# TSOC_GROVEY_UART.net
KiCad netlist of a schematic drawn in EAGLE
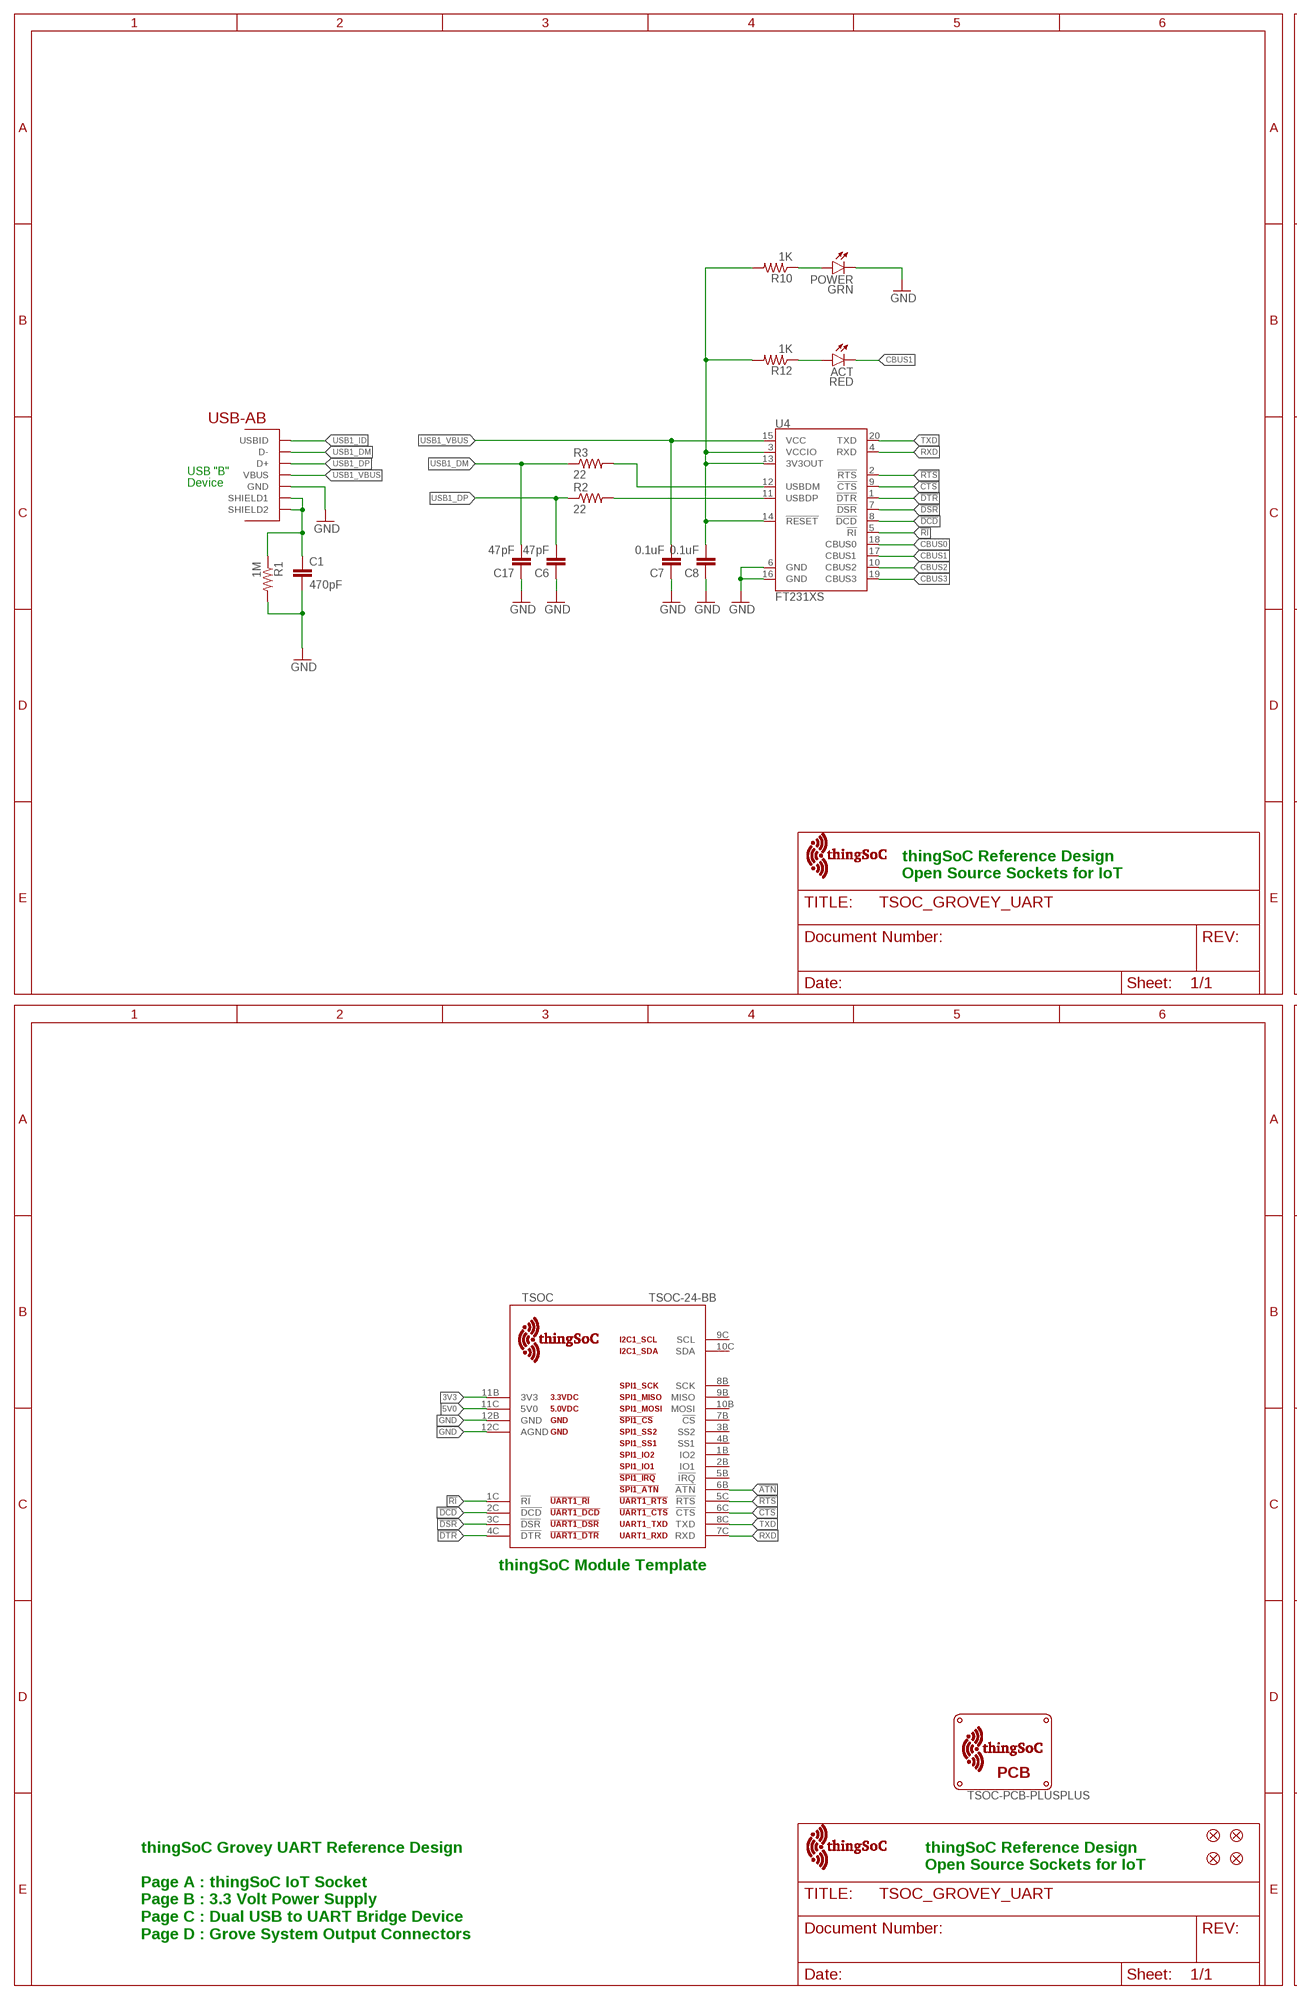
[diagram p0: schematic, sheet 1, part 1 of 2]
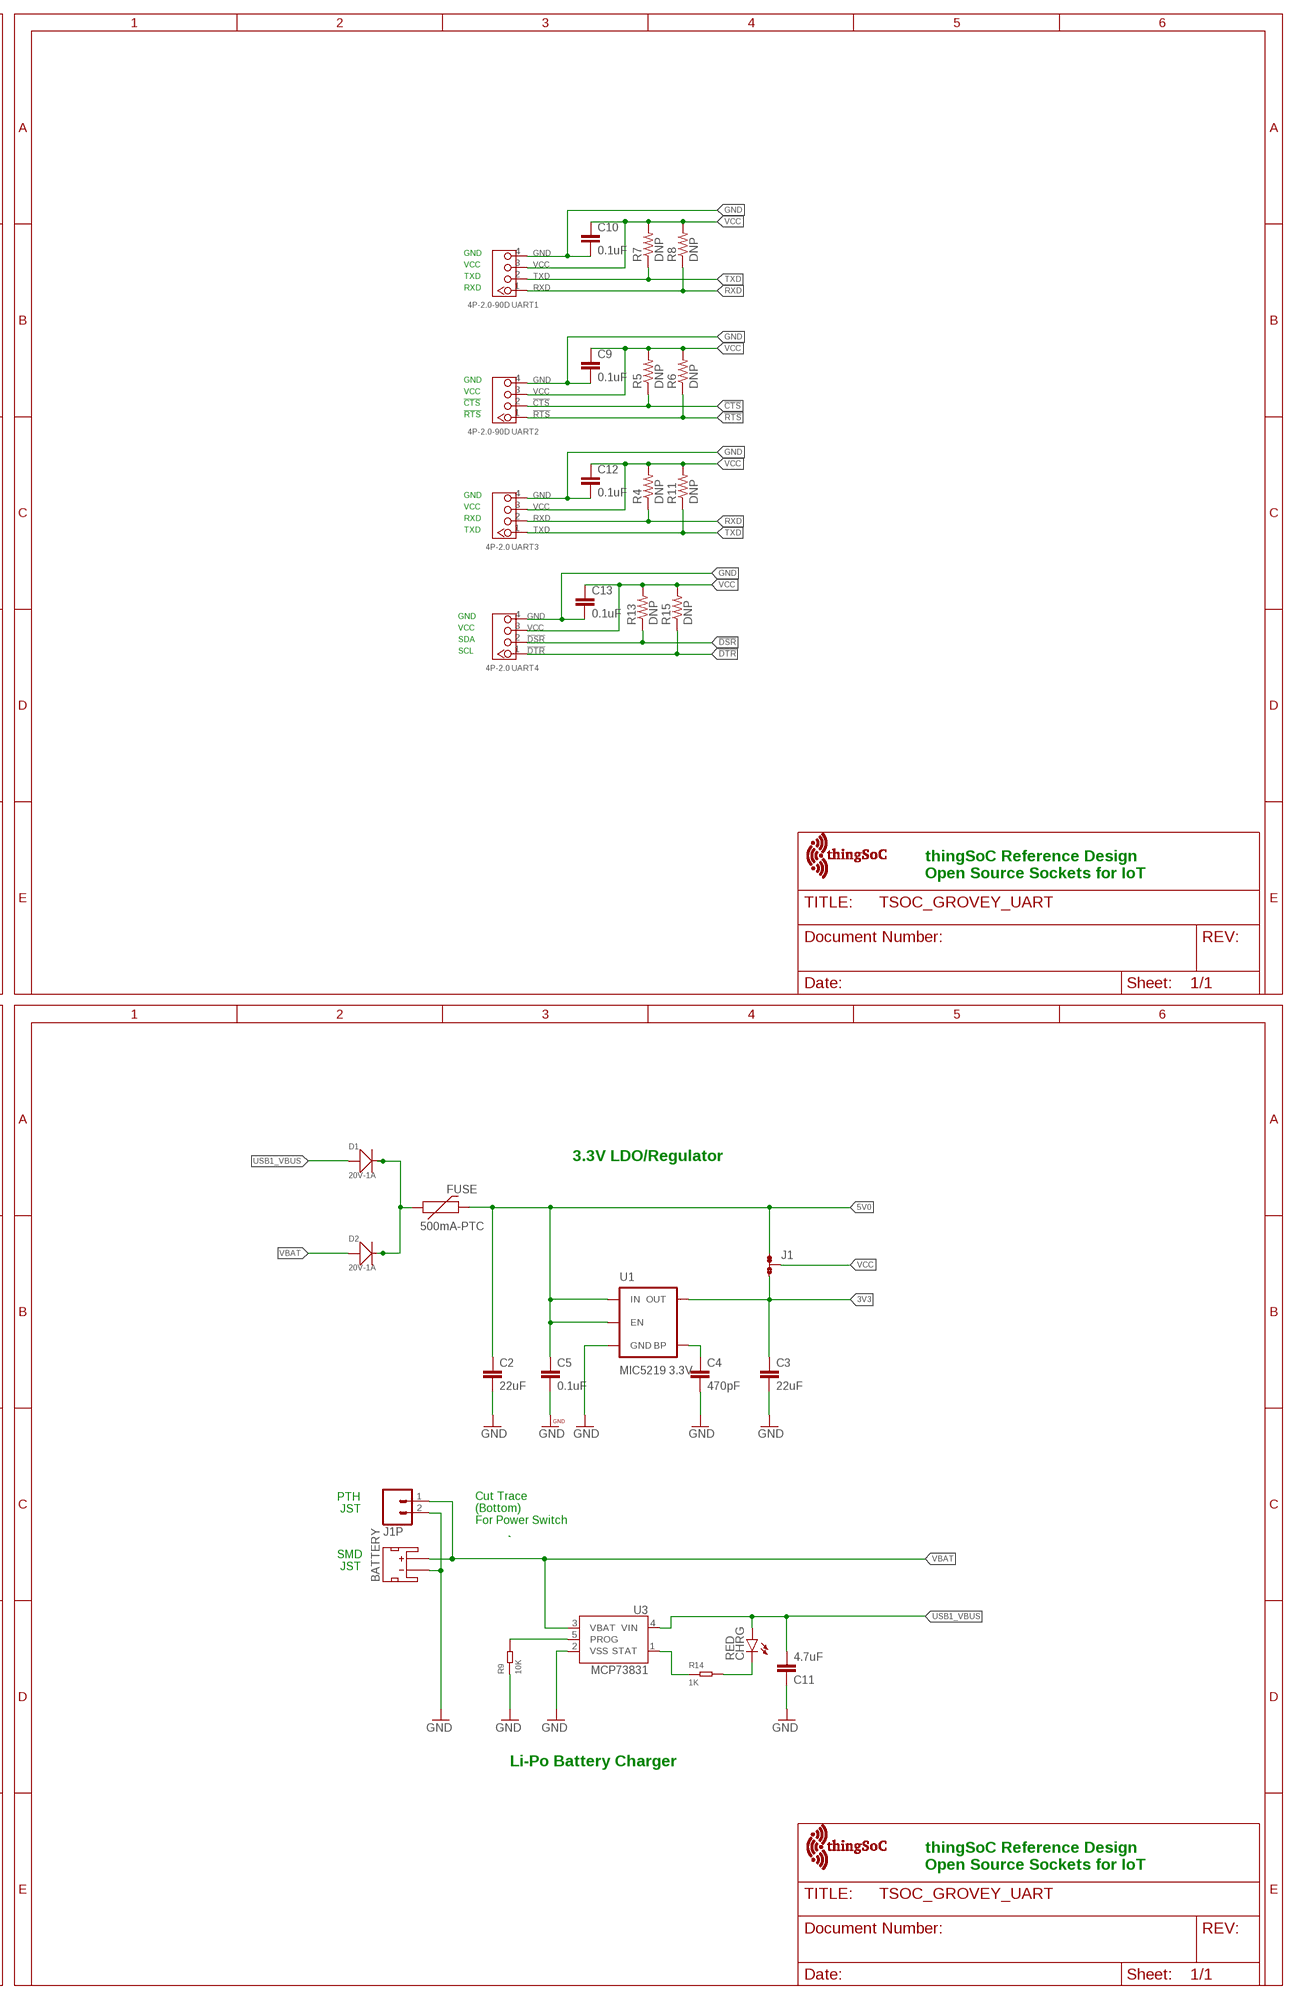
[diagram p1: schematic, sheet 1, part 2 of 2]

(export (version "E")
  (design (tool "Eeschema 10.0.6"))
  (components
    (comp (ref "ACT")
      (value "RED")
      (footprint "eagle-import:LED-0603")
      (libsource (lib "eagle-import") (part "LED0603"))
    )
    (comp (ref "BATTERY")
      (value "JST_2MM_MALE")
      (footprint "eagle-import:JST-2-SMD")
      (libsource (lib "eagle-import") (part "JST_2MM_MALE"))
    )
    (comp (ref "C1")
      (value "470pF")
      (footprint "eagle-import:EIA-0603")
      (libsource (lib "eagle-import") (part "CAP-0603"))
    )
    (comp (ref "C2")
      (value "22uF")
      (footprint "eagle-import:EIA-1206")
      (libsource (lib "eagle-import") (part "CAP-1206"))
    )
    (comp (ref "C3")
      (value "22uF")
      (footprint "eagle-import:EIA-1206")
      (libsource (lib "eagle-import") (part "CAP-1206"))
    )
    (comp (ref "C4")
      (value "470pF")
      (footprint "eagle-import:EIA-0603")
      (libsource (lib "eagle-import") (part "CAP-0603"))
    )
    (comp (ref "C5")
      (value "0.1uF")
      (footprint "eagle-import:EIA-0603")
      (libsource (lib "eagle-import") (part "CAP-0603"))
    )
    (comp (ref "C6")
      (value "47pF")
      (footprint "eagle-import:EIA-0603")
      (libsource (lib "eagle-import") (part "CAP-0603"))
    )
    (comp (ref "C7")
      (value "0.1uF")
      (footprint "eagle-import:EIA-0603")
      (libsource (lib "eagle-import") (part "CAP-0603"))
    )
    (comp (ref "C8")
      (value "0.1uF")
      (footprint "eagle-import:EIA-0603")
      (libsource (lib "eagle-import") (part "CAP-0603"))
    )
    (comp (ref "C9")
      (value "0.1uF")
      (footprint "eagle-import:0603-CAP")
      (libsource (lib "eagle-import") (part "CAP0603-CAP"))
    )
    (comp (ref "C10")
      (value "0.1uF")
      (footprint "eagle-import:0603-CAP")
      (libsource (lib "eagle-import") (part "CAP0603-CAP"))
    )
    (comp (ref "C11")
      (value "4.7uF")
      (footprint "eagle-import:0402-CAP")
      (libsource (lib "eagle-import") (part "TSOC-ESP8266-BASE_CAP0402-CAP"))
    )
    (comp (ref "C12")
      (value "0.1uF")
      (footprint "eagle-import:0603-CAP")
      (libsource (lib "eagle-import") (part "CAP0603-CAP"))
    )
    (comp (ref "C13")
      (value "0.1uF")
      (footprint "eagle-import:0603-CAP")
      (libsource (lib "eagle-import") (part "CAP0603-CAP"))
    )
    (comp (ref "C17")
      (value "47pF")
      (footprint "eagle-import:EIA-0603")
      (libsource (lib "eagle-import") (part "CAP-0603"))
    )
    (comp (ref "CHRG")
      (value "RED")
      (footprint "eagle-import:LED-0603")
      (libsource (lib "eagle-import") (part "LED0603"))
    )
    (comp (ref "D1")
      (value "20V-1A")
      (footprint "eagle-import:SOD-123")
      (fields (field (name "MPN") "B5819W"))
      (libsource (lib "eagle-import") (part "SMD-DIODE-SCHOTTKY-20V-1A(SOD-123)"))
    )
    (comp (ref "D2")
      (value "20V-1A")
      (footprint "eagle-import:SOD-123")
      (fields (field (name "MPN") "B5819W"))
      (libsource (lib "eagle-import") (part "SMD-DIODE-SCHOTTKY-20V-1A(SOD-123)"))
    )
    (comp (ref "FID1")
      (value "FIDUCIALUFIDUCIAL")
      (footprint "eagle-import:MICRO-FIDUCIAL")
      (libsource (lib "eagle-import") (part "FIDUCIALUFIDUCIAL"))
    )
    (comp (ref "FID2")
      (value "FIDUCIALUFIDUCIAL")
      (footprint "eagle-import:MICRO-FIDUCIAL")
      (libsource (lib "eagle-import") (part "FIDUCIALUFIDUCIAL"))
    )
    (comp (ref "FID3")
      (value "FIDUCIALUFIDUCIAL")
      (footprint "eagle-import:MICRO-FIDUCIAL")
      (libsource (lib "eagle-import") (part "FIDUCIALUFIDUCIAL"))
    )
    (comp (ref "FID4")
      (value "FIDUCIALUFIDUCIAL")
      (footprint "eagle-import:MICRO-FIDUCIAL")
      (libsource (lib "eagle-import") (part "FIDUCIALUFIDUCIAL"))
    )
    (comp (ref "FUSE")
      (value "500mA-PTC")
      (footprint "eagle-import:PTC-1206")
      (libsource (lib "eagle-import") (part "PTCSMD"))
    )
    (comp (ref "J1")
      (value "JMP-3-1_2")
      (footprint "eagle-import:JMP-3-1_2")
      (libsource (lib "eagle-import") (part "JMP-3-1_2"))
    )
    (comp (ref "J1P")
      (value "M02-JST-2-PTH-NO_SILK")
      (footprint "eagle-import:JST-2-PTH-NS")
      (libsource (lib "eagle-import") (part "M02-JST-2-PTH-NO_SILK"))
    )
    (comp (ref "POWER")
      (value "GRN")
      (footprint "eagle-import:LED-0603")
      (libsource (lib "eagle-import") (part "LED0603"))
    )
    (comp (ref "R1")
      (value "1M")
      (footprint "eagle-import:EIA-0603")
      (libsource (lib "eagle-import") (part "RESISTOR-0603"))
    )
    (comp (ref "R2")
      (value "22")
      (footprint "eagle-import:EIA-0603")
      (libsource (lib "eagle-import") (part "RESISTOR-0603"))
    )
    (comp (ref "R3")
      (value "22")
      (footprint "eagle-import:EIA-0603")
      (libsource (lib "eagle-import") (part "RESISTOR-0603"))
    )
    (comp (ref "R4")
      (value "DNP")
      (footprint "eagle-import:0603-RES")
      (libsource (lib "eagle-import") (part "RESISTOR0603-RES"))
    )
    (comp (ref "R5")
      (value "DNP")
      (footprint "eagle-import:0603-RES")
      (libsource (lib "eagle-import") (part "RESISTOR0603-RES"))
    )
    (comp (ref "R6")
      (value "DNP")
      (footprint "eagle-import:0603-RES")
      (libsource (lib "eagle-import") (part "RESISTOR0603-RES"))
    )
    (comp (ref "R7")
      (value "DNP")
      (footprint "eagle-import:0603-RES")
      (libsource (lib "eagle-import") (part "RESISTOR0603-RES"))
    )
    (comp (ref "R8")
      (value "DNP")
      (footprint "eagle-import:0603-RES")
      (libsource (lib "eagle-import") (part "RESISTOR0603-RES"))
    )
    (comp (ref "R9")
      (value "10K")
      (footprint "eagle-import:R0603")
      (fields (field (name "MPN") "RC0603FR-0710KL"))
      (libsource (lib "eagle-import") (part "SMD-RES-10K-1%-1/10W(0603)"))
    )
    (comp (ref "R10")
      (value "1K")
      (footprint "eagle-import:EIA-0603")
      (libsource (lib "eagle-import") (part "RESISTOR-0603"))
    )
    (comp (ref "R11")
      (value "DNP")
      (footprint "eagle-import:0603-RES")
      (libsource (lib "eagle-import") (part "RESISTOR0603-RES"))
    )
    (comp (ref "R12")
      (value "1K")
      (footprint "eagle-import:EIA-0603")
      (libsource (lib "eagle-import") (part "RESISTOR-0603"))
    )
    (comp (ref "R13")
      (value "DNP")
      (footprint "eagle-import:0603-RES")
      (libsource (lib "eagle-import") (part "RESISTOR0603-RES"))
    )
    (comp (ref "R14")
      (value "1K")
      (footprint "eagle-import:R0603")
      (fields (field (name "MPN") "RC0603FR-071KL"))
      (libsource (lib "eagle-import") (part "SMD-RES-1K-1%-1/10W(0603)"))
    )
    (comp (ref "R15")
      (value "DNP")
      (footprint "eagle-import:0603-RES")
      (libsource (lib "eagle-import") (part "RESISTOR0603-RES"))
    )
    (comp (ref "TSOC")
      (value "TSOC-24-BB")
      (footprint "eagle-import:TSOC-BB-S24")
      (libsource (lib "eagle-import") (part "TSOC-24-BB"))
    )
    (comp (ref "U$3")
      (value "TSOC-LOGO-LRG")
      (footprint "eagle-import:TSOC-LOGO-LRG")
      (libsource (lib "eagle-import") (part "TSOC-LOGO-LRG"))
    )
    (comp (ref "U$4")
      (value "TSOC-LOGO")
      (footprint "eagle-import:TSOC-LOGO-BLANK")
      (libsource (lib "eagle-import") (part "TSOC-LOGO"))
    )
    (comp (ref "U$5")
      (value "TSOC-LOGO")
      (footprint "eagle-import:TSOC-LOGO-BLANK")
      (libsource (lib "eagle-import") (part "TSOC-LOGO"))
    )
    (comp (ref "U$6")
      (value "TSOC-LOGO")
      (footprint "eagle-import:TSOC-LOGO-BLANK")
      (libsource (lib "eagle-import") (part "TSOC-LOGO"))
    )
    (comp (ref "U$8")
      (value "TSOC-PCB-PLUSPLUS")
      (footprint "eagle-import:TSOC-BB-BRD-PLUS-PLUS-DIM")
      (libsource (lib "eagle-import") (part "TSOC-PCB-PLUSPLUS"))
    )
    (comp (ref "U1")
      (value "MIC5219 3.3V")
      (footprint "eagle-import:SOT23-5")
      (libsource (lib "eagle-import") (part "V_REG_MIC52193.3V"))
    )
    (comp (ref "U3")
      (value "MCP73831")
      (footprint "eagle-import:SOT23-5")
      (libsource (lib "eagle-import") (part "MCP73831"))
    )
    (comp (ref "U4")
      (value "FT231XS")
      (footprint "eagle-import:SSOP20_L")
      (libsource (lib "eagle-import") (part "FT231XS"))
    )
    (comp (ref "UART1")
      (value "4P-2.0-90D")
      (footprint "eagle-import:HW4-2.0-90D")
      (libsource (lib "eagle-import") (part "GROVE-CONNECTOR-DIP-90D(4P-2.0)"))
    )
    (comp (ref "UART2")
      (value "4P-2.0-90D")
      (footprint "eagle-import:HW4-2.0-90D")
      (libsource (lib "eagle-import") (part "GROVE-CONNECTOR-DIP-90D(4P-2.0)"))
    )
    (comp (ref "UART3")
      (value "4P-2.0")
      (footprint "eagle-import:HW4-2.0")
      (libsource (lib "eagle-import") (part "GROVE-CONNECTOR-DIP(4P-2.0)"))
    )
    (comp (ref "UART4")
      (value "4P-2.0")
      (footprint "eagle-import:HW4-2.0")
      (libsource (lib "eagle-import") (part "GROVE-CONNECTOR-DIP(4P-2.0)"))
    )
    (comp (ref "USB")
      (value "USB_AB")
      (footprint "eagle-import:USB-AB-MICRO-SMD")
      (libsource (lib "eagle-import") (part "USB_AB"))
    )
  )
  (nets
    (net (code "1") (name "/~{ATN}") (class "Default")
      (node (ref "TSOC") (pin "6B") (pinfunction "~{ATN}_6B") (pintype "bidirectional"))
    )
    (net (code "2") (name "/~{CTS}") (class "Default")
      (node (ref "R5") (pin "1") (pinfunction "1_1") (pintype "passive"))
      (node (ref "TSOC") (pin "6C") (pinfunction "~{CTS}_6C") (pintype "bidirectional"))
      (node (ref "U4") (pin "9") (pinfunction "~{CTS}_9") (pintype "bidirectional"))
      (node (ref "UART2") (pin "2") (pinfunction "2_2") (pintype "bidirectional"))
    )
    (net (code "3") (name "/~{DCD}") (class "Default")
      (node (ref "TSOC") (pin "2C") (pinfunction "~{DCD}_2C") (pintype "bidirectional"))
      (node (ref "U4") (pin "8") (pinfunction "~{DCD}_8") (pintype "bidirectional"))
    )
    (net (code "4") (name "/~{DSR}") (class "Default")
      (node (ref "R13") (pin "1") (pinfunction "1_1") (pintype "passive"))
      (node (ref "TSOC") (pin "3C") (pinfunction "~{DSR}_3C") (pintype "bidirectional"))
      (node (ref "U4") (pin "7") (pinfunction "~{DSR}_7") (pintype "bidirectional"))
      (node (ref "UART4") (pin "2") (pinfunction "2_2") (pintype "bidirectional"))
    )
    (net (code "5") (name "/~{DTR}") (class "Default")
      (node (ref "R15") (pin "1") (pinfunction "1_1") (pintype "passive"))
      (node (ref "TSOC") (pin "4C") (pinfunction "~{DTR}_4C") (pintype "bidirectional"))
      (node (ref "U4") (pin "1") (pinfunction "~{DTR}_1") (pintype "bidirectional"))
      (node (ref "UART4") (pin "1") (pinfunction "1_1") (pintype "bidirectional"))
    )
    (net (code "6") (name "/~{RI}") (class "Default")
      (node (ref "TSOC") (pin "1C") (pinfunction "~{RI}_1C") (pintype "bidirectional"))
      (node (ref "U4") (pin "5") (pinfunction "~{RI}_5") (pintype "bidirectional"))
    )
    (net (code "7") (name "/~{RTS}") (class "Default")
      (node (ref "R6") (pin "1") (pinfunction "1_1") (pintype "passive"))
      (node (ref "TSOC") (pin "5C") (pinfunction "~{RTS}_5C") (pintype "bidirectional"))
      (node (ref "U4") (pin "2") (pinfunction "~{RTS}_2") (pintype "bidirectional"))
      (node (ref "UART2") (pin "1") (pinfunction "1_1") (pintype "bidirectional"))
    )
    (net (code "8") (name "3V3") (class "Default")
      (node (ref "C3") (pin "1") (pinfunction "1_1") (pintype "passive"))
      (node (ref "J1") (pin "3") (pinfunction "3_3") (pintype "passive"))
      (node (ref "TSOC") (pin "11B") (pinfunction "3V3_11B") (pintype "bidirectional"))
      (node (ref "U1") (pin "5") (pinfunction "OUT_5") (pintype "passive"))
    )
    (net (code "9") (name "5V0") (class "Default")
      (node (ref "C2") (pin "1") (pinfunction "1_1") (pintype "passive"))
      (node (ref "C5") (pin "1") (pinfunction "1_1") (pintype "passive"))
      (node (ref "FUSE") (pin "2") (pinfunction "2_2") (pintype "bidirectional"))
      (node (ref "J1") (pin "1") (pinfunction "1_1") (pintype "passive"))
      (node (ref "TSOC") (pin "11C") (pinfunction "5V0_11C") (pintype "bidirectional"))
      (node (ref "U1") (pin "1") (pinfunction "IN_1") (pintype "input"))
      (node (ref "U1") (pin "3") (pinfunction "EN_3") (pintype "input"))
    )
    (net (code "10") (name "CBUS0") (class "Default")
      (node (ref "U4") (pin "18") (pinfunction "CBUS0_18") (pintype "bidirectional"))
    )
    (net (code "11") (name "CBUS1") (class "Default")
      (node (ref "ACT") (pin "C") (pinfunction "C_C") (pintype "passive"))
      (node (ref "U4") (pin "17") (pinfunction "CBUS1_17") (pintype "bidirectional"))
    )
    (net (code "12") (name "CBUS2") (class "Default")
      (node (ref "U4") (pin "10") (pinfunction "CBUS2_10") (pintype "bidirectional"))
    )
    (net (code "13") (name "CBUS3") (class "Default")
      (node (ref "U4") (pin "19") (pinfunction "CBUS3_19") (pintype "bidirectional"))
    )
    (net (code "14") (name "GND") (class "Default")
      (node (ref "BATTERY") (pin "1") (pinfunction "-_1") (pintype "bidirectional"))
      (node (ref "C1") (pin "2") (pinfunction "2_2") (pintype "passive"))
      (node (ref "C10") (pin "2") (pinfunction "2_2") (pintype "passive"))
      (node (ref "C11") (pin "1") (pinfunction "1_1") (pintype "passive"))
      (node (ref "C12") (pin "2") (pinfunction "2_2") (pintype "passive"))
      (node (ref "C13") (pin "2") (pinfunction "2_2") (pintype "passive"))
      (node (ref "C17") (pin "1") (pinfunction "1_1") (pintype "passive"))
      (node (ref "C2") (pin "2") (pinfunction "2_2") (pintype "passive"))
      (node (ref "C3") (pin "2") (pinfunction "2_2") (pintype "passive"))
      (node (ref "C4") (pin "2") (pinfunction "2_2") (pintype "passive"))
      (node (ref "C5") (pin "2") (pinfunction "2_2") (pintype "passive"))
      (node (ref "C6") (pin "1") (pinfunction "1_1") (pintype "passive"))
      (node (ref "C7") (pin "1") (pinfunction "1_1") (pintype "passive"))
      (node (ref "C8") (pin "1") (pinfunction "1_1") (pintype "passive"))
      (node (ref "C9") (pin "2") (pinfunction "2_2") (pintype "passive"))
      (node (ref "J1P") (pin "2") (pinfunction "2_2") (pintype "passive"))
      (node (ref "POWER") (pin "C") (pinfunction "C_C") (pintype "passive"))
      (node (ref "R1") (pin "2") (pinfunction "2_2") (pintype "passive"))
      (node (ref "R9") (pin "1") (pinfunction "1_1") (pintype "passive"))
      (node (ref "TSOC") (pin "12B") (pinfunction "GND_12B") (pintype "bidirectional"))
      (node (ref "TSOC") (pin "12C") (pinfunction "AGND_12C") (pintype "bidirectional"))
      (node (ref "U1") (pin "2") (pinfunction "GND_2") (pintype "input"))
      (node (ref "U3") (pin "2") (pinfunction "VSS_2") (pintype "power_in"))
      (node (ref "U4") (pin "16") (pinfunction "GND_16") (pintype "bidirectional"))
      (node (ref "U4") (pin "6") (pinfunction "GND_6") (pintype "bidirectional"))
      (node (ref "UART1") (pin "4") (pinfunction "4_4") (pintype "bidirectional"))
      (node (ref "UART2") (pin "4") (pinfunction "4_4") (pintype "bidirectional"))
      (node (ref "UART3") (pin "4") (pinfunction "4_4") (pintype "bidirectional"))
      (node (ref "UART4") (pin "4") (pinfunction "4_4") (pintype "bidirectional"))
      (node (ref "USB") (pin "GND") (pinfunction "GND_GND") (pintype "bidirectional"))
    )
    (net (code "15") (name "Net-(ACT-PadA)") (class "Default")
      (node (ref "ACT") (pin "A") (pinfunction "A_A") (pintype "passive"))
      (node (ref "R12") (pin "1") (pinfunction "1_1") (pintype "passive"))
    )
    (net (code "16") (name "Net-(C1-Pad1)") (class "Default")
      (node (ref "C1") (pin "1") (pinfunction "1_1") (pintype "passive"))
      (node (ref "R1") (pin "1") (pinfunction "1_1") (pintype "passive"))
      (node (ref "USB") (pin "SHIELD1") (pinfunction "SHIELD1_SHIELD1") (pintype "bidirectional"))
      (node (ref "USB") (pin "SHIELD2") (pinfunction "SHIELD2_SHIELD2") (pintype "bidirectional"))
    )
    (net (code "17") (name "Net-(CHRG-PadC)") (class "Default")
      (node (ref "CHRG") (pin "C") (pinfunction "C_C") (pintype "passive"))
      (node (ref "R14") (pin "2") (pinfunction "2_2") (pintype "passive"))
    )
    (net (code "18") (name "Net-(D1-Pad-)") (class "Default")
      (node (ref "D1") (pin "-") (pinfunction "-_-") (pintype "passive"))
      (node (ref "D2") (pin "-") (pinfunction "-_-") (pintype "passive"))
      (node (ref "FUSE") (pin "1") (pinfunction "1_1") (pintype "bidirectional"))
    )
    (net (code "19") (name "Net-(POWER-PadA)") (class "Default")
      (node (ref "POWER") (pin "A") (pinfunction "A_A") (pintype "passive"))
      (node (ref "R10") (pin "1") (pinfunction "1_1") (pintype "passive"))
    )
    (net (code "20") (name "Net-(U1-BP)") (class "Default")
      (node (ref "C4") (pin "1") (pinfunction "1_1") (pintype "passive"))
      (node (ref "U1") (pin "4") (pinfunction "BP_4") (pintype "input"))
    )
    (net (code "21") (name "Net-(U3-PROG)") (class "Default")
      (node (ref "R9") (pin "2") (pinfunction "2_2") (pintype "passive"))
      (node (ref "U3") (pin "5") (pinfunction "PROG_5") (pintype "input"))
    )
    (net (code "22") (name "Net-(U3-STAT)") (class "Default")
      (node (ref "R14") (pin "1") (pinfunction "1_1") (pintype "passive"))
      (node (ref "U3") (pin "1") (pinfunction "STAT_1") (pintype "output"))
    )
    (net (code "23") (name "Net-(U4-3V3OUT)") (class "Default")
      (node (ref "C8") (pin "2") (pinfunction "2_2") (pintype "passive"))
      (node (ref "R10") (pin "2") (pinfunction "2_2") (pintype "passive"))
      (node (ref "R12") (pin "2") (pinfunction "2_2") (pintype "passive"))
      (node (ref "U4") (pin "13") (pinfunction "3V3OUT_13") (pintype "bidirectional"))
      (node (ref "U4") (pin "14") (pinfunction "~{RESET}_14") (pintype "bidirectional"))
      (node (ref "U4") (pin "3") (pinfunction "VCCIO_3") (pintype "bidirectional"))
    )
    (net (code "24") (name "Net-(U4-USBDM)") (class "Default")
      (node (ref "R3") (pin "2") (pinfunction "2_2") (pintype "passive"))
      (node (ref "U4") (pin "12") (pinfunction "USBDM_12") (pintype "bidirectional"))
    )
    (net (code "25") (name "Net-(U4-USBDP)") (class "Default")
      (node (ref "R2") (pin "2") (pinfunction "2_2") (pintype "passive"))
      (node (ref "U4") (pin "11") (pinfunction "USBDP_11") (pintype "bidirectional"))
    )
    (net (code "26") (name "RXD") (class "Default")
      (node (ref "R4") (pin "1") (pinfunction "1_1") (pintype "passive"))
      (node (ref "R8") (pin "1") (pinfunction "1_1") (pintype "passive"))
      (node (ref "TSOC") (pin "7C") (pinfunction "RXD_7C") (pintype "bidirectional"))
      (node (ref "U4") (pin "4") (pinfunction "RXD_4") (pintype "bidirectional"))
      (node (ref "UART1") (pin "1") (pinfunction "1_1") (pintype "bidirectional"))
      (node (ref "UART3") (pin "2") (pinfunction "2_2") (pintype "bidirectional"))
    )
    (net (code "27") (name "TXD") (class "Default")
      (node (ref "R11") (pin "1") (pinfunction "1_1") (pintype "passive"))
      (node (ref "R7") (pin "1") (pinfunction "1_1") (pintype "passive"))
      (node (ref "TSOC") (pin "8C") (pinfunction "TXD_8C") (pintype "bidirectional"))
      (node (ref "U4") (pin "20") (pinfunction "TXD_20") (pintype "bidirectional"))
      (node (ref "UART1") (pin "2") (pinfunction "2_2") (pintype "bidirectional"))
      (node (ref "UART3") (pin "1") (pinfunction "1_1") (pintype "bidirectional"))
    )
    (net (code "28") (name "USB1_DM") (class "Default")
      (node (ref "C17") (pin "2") (pinfunction "2_2") (pintype "passive"))
      (node (ref "R3") (pin "1") (pinfunction "1_1") (pintype "passive"))
      (node (ref "USB") (pin "D-") (pinfunction "D-_D-") (pintype "bidirectional"))
    )
    (net (code "29") (name "USB1_DP") (class "Default")
      (node (ref "C6") (pin "2") (pinfunction "2_2") (pintype "passive"))
      (node (ref "R2") (pin "1") (pinfunction "1_1") (pintype "passive"))
      (node (ref "USB") (pin "D+") (pinfunction "D+_D+") (pintype "bidirectional"))
    )
    (net (code "30") (name "USB1_ID") (class "Default")
      (node (ref "USB") (pin "ID") (pinfunction "USBID_ID") (pintype "bidirectional"))
    )
    (net (code "31") (name "USB1_VBUS") (class "Default")
      (node (ref "C11") (pin "2") (pinfunction "2_2") (pintype "passive"))
      (node (ref "C7") (pin "2") (pinfunction "2_2") (pintype "passive"))
      (node (ref "CHRG") (pin "A") (pinfunction "A_A") (pintype "passive"))
      (node (ref "D1") (pin "+") (pinfunction "+_+") (pintype "passive"))
      (node (ref "U3") (pin "4") (pinfunction "VIN_4") (pintype "power_in"))
      (node (ref "U4") (pin "15") (pinfunction "VCC_15") (pintype "bidirectional"))
      (node (ref "USB") (pin "VBUS") (pinfunction "VBUS_VBUS") (pintype "bidirectional"))
    )
    (net (code "32") (name "VBAT") (class "Default")
      (node (ref "BATTERY") (pin "2") (pinfunction "+_2") (pintype "bidirectional"))
      (node (ref "D2") (pin "+") (pinfunction "+_+") (pintype "passive"))
      (node (ref "J1P") (pin "1") (pinfunction "1_1") (pintype "passive"))
      (node (ref "U3") (pin "3") (pinfunction "VBAT_3") (pintype "power_in"))
    )
    (net (code "33") (name "VCC") (class "Default")
      (node (ref "C10") (pin "1") (pinfunction "1_1") (pintype "passive"))
      (node (ref "C12") (pin "1") (pinfunction "1_1") (pintype "passive"))
      (node (ref "C13") (pin "1") (pinfunction "1_1") (pintype "passive"))
      (node (ref "C9") (pin "1") (pinfunction "1_1") (pintype "passive"))
      (node (ref "J1") (pin "2") (pinfunction "2_2") (pintype "passive"))
      (node (ref "R11") (pin "2") (pinfunction "2_2") (pintype "passive"))
      (node (ref "R13") (pin "2") (pinfunction "2_2") (pintype "passive"))
      (node (ref "R15") (pin "2") (pinfunction "2_2") (pintype "passive"))
      (node (ref "R4") (pin "2") (pinfunction "2_2") (pintype "passive"))
      (node (ref "R5") (pin "2") (pinfunction "2_2") (pintype "passive"))
      (node (ref "R6") (pin "2") (pinfunction "2_2") (pintype "passive"))
      (node (ref "R7") (pin "2") (pinfunction "2_2") (pintype "passive"))
      (node (ref "R8") (pin "2") (pinfunction "2_2") (pintype "passive"))
      (node (ref "UART1") (pin "3") (pinfunction "3_3") (pintype "bidirectional"))
      (node (ref "UART2") (pin "3") (pinfunction "3_3") (pintype "bidirectional"))
      (node (ref "UART3") (pin "3") (pinfunction "3_3") (pintype "bidirectional"))
      (node (ref "UART4") (pin "3") (pinfunction "3_3") (pintype "bidirectional"))
    )
    (net (code "34") (name "unconnected-(BATTERY-PAD1-PadNC1)") (class "Default")
      (node (ref "BATTERY") (pin "NC1") (pinfunction "PAD1_NC1") (pintype "bidirectional"))
    )
    (net (code "35") (name "unconnected-(BATTERY-PAD2-PadNC2)") (class "Default")
      (node (ref "BATTERY") (pin "NC2") (pinfunction "PAD2_NC2") (pintype "bidirectional"))
    )
    (net (code "36") (name "unconnected-(TSOC-IO1-Pad2B)") (class "Default")
      (node (ref "TSOC") (pin "2B") (pinfunction "IO1_2B") (pintype "bidirectional"))
    )
    (net (code "37") (name "unconnected-(TSOC-IO2-Pad1B)") (class "Default")
      (node (ref "TSOC") (pin "1B") (pinfunction "IO2_1B") (pintype "bidirectional"))
    )
    (net (code "38") (name "unconnected-(TSOC-MISO-Pad9B)") (class "Default")
      (node (ref "TSOC") (pin "9B") (pinfunction "MISO_9B") (pintype "bidirectional"))
    )
    (net (code "39") (name "unconnected-(TSOC-MOSI-Pad10B)") (class "Default")
      (node (ref "TSOC") (pin "10B") (pinfunction "MOSI_10B") (pintype "bidirectional"))
    )
    (net (code "40") (name "unconnected-(TSOC-SCK-Pad8B)") (class "Default")
      (node (ref "TSOC") (pin "8B") (pinfunction "SCK_8B") (pintype "bidirectional"))
    )
    (net (code "41") (name "unconnected-(TSOC-SCL-Pad9C)") (class "Default")
      (node (ref "TSOC") (pin "9C") (pinfunction "SCL_9C") (pintype "bidirectional"))
    )
    (net (code "42") (name "unconnected-(TSOC-SDA-Pad10C)") (class "Default")
      (node (ref "TSOC") (pin "10C") (pinfunction "SDA_10C") (pintype "bidirectional"))
    )
    (net (code "43") (name "unconnected-(TSOC-SS1-Pad4B)") (class "Default")
      (node (ref "TSOC") (pin "4B") (pinfunction "SS1_4B") (pintype "bidirectional"))
    )
    (net (code "44") (name "unconnected-(TSOC-SS2-Pad3B)") (class "Default")
      (node (ref "TSOC") (pin "3B") (pinfunction "SS2_3B") (pintype "bidirectional"))
    )
    (net (code "45") (name "unconnected-(TSOC-~{CS}-Pad7B)") (class "Default")
      (node (ref "TSOC") (pin "7B") (pinfunction "~{CS}_7B") (pintype "bidirectional"))
    )
    (net (code "46") (name "unconnected-(TSOC-~{IRQ}-Pad5B)") (class "Default")
      (node (ref "TSOC") (pin "5B") (pinfunction "~{IRQ}_5B") (pintype "bidirectional"))
    )
  )
)
